# BBallboard.net
KiCad netlist of a schematic drawn in EAGLE
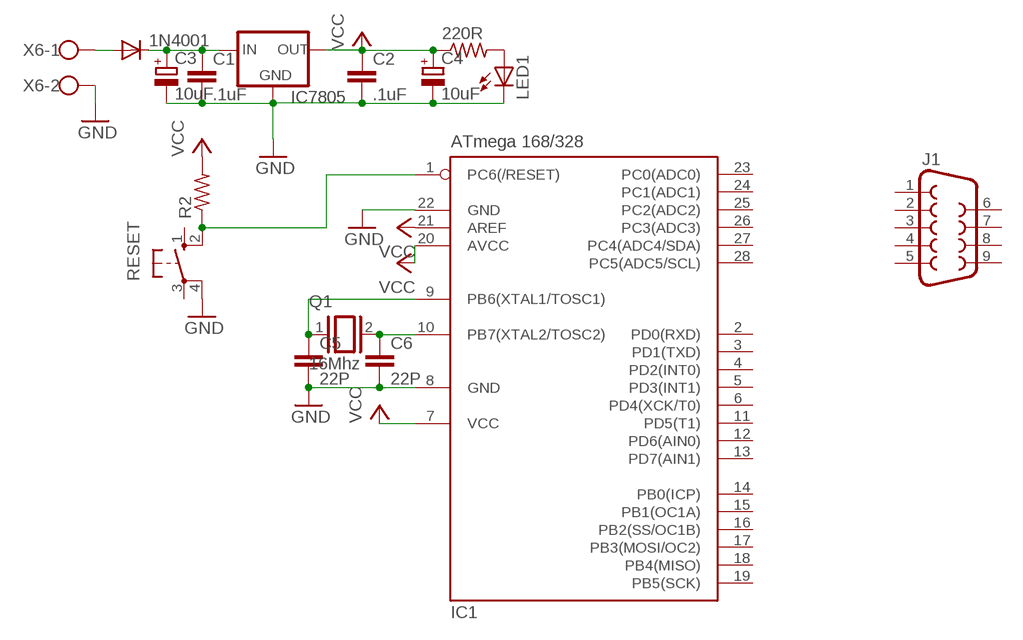
[diagram p0: schematic, sheet 1]

(export (version "E")
  (design (tool "Eeschema 10.0.6"))
  (components
    (comp (ref "1N4001")
      (value "BYT85")
      (footprint "eagle-import:DO220S")
      (libsource (lib "eagle-import") (part "BYT85"))
    )
    (comp (ref "220R")
      (value "R-US_0204/7")
      (footprint "eagle-import:0204_7")
      (libsource (lib "eagle-import") (part "R-US_0204/7"))
    )
    (comp (ref "C1")
      (value ".1uF")
      (footprint "eagle-import:C025-024X044")
      (libsource (lib "eagle-import") (part "C-EU025-024X044"))
    )
    (comp (ref "C2")
      (value ".1uF")
      (footprint "eagle-import:C025-024X044")
      (libsource (lib "eagle-import") (part "C-EU025-024X044"))
    )
    (comp (ref "C3")
      (value "10uF")
      (footprint "eagle-import:E1,8-4")
      (libsource (lib "eagle-import") (part "CPOL-EUE1.8-4"))
    )
    (comp (ref "C4")
      (value "10uF")
      (footprint "eagle-import:E1,8-4")
      (libsource (lib "eagle-import") (part "CPOL-EUE1.8-4"))
    )
    (comp (ref "C5")
      (value "22P")
      (footprint "eagle-import:C025-024X044")
      (libsource (lib "eagle-import") (part "C-EU025-024X044"))
    )
    (comp (ref "C6")
      (value "22P")
      (footprint "eagle-import:C025-024X044")
      (libsource (lib "eagle-import") (part "C-EU025-024X044"))
    )
    (comp (ref "IC1")
      (value "ATmega 168/328")
      (footprint "eagle-import:DIL28-3")
      (libsource (lib "eagle-import") (part "MEGA8-P"))
    )
    (comp (ref "IC7805")
      (value "78XXS")
      (footprint "eagle-import:78XXS")
      (libsource (lib "eagle-import") (part "78XXS"))
    )
    (comp (ref "J1")
      (value "DB9FEMALE")
      (footprint "eagle-import:DB9")
      (libsource (lib "eagle-import") (part "DB9FEMALE"))
    )
    (comp (ref "LED1")
      (value "LED3MM")
      (footprint "eagle-import:LED3MM")
      (libsource (lib "eagle-import") (part "LED3MM"))
    )
    (comp (ref "Q1")
      (value "16Mhz")
      (footprint "eagle-import:QS")
      (libsource (lib "eagle-import") (part "XTAL/S"))
    )
    (comp (ref "R2")
      (value "R-US_0204/7")
      (footprint "eagle-import:0204_7")
      (libsource (lib "eagle-import") (part "R-US_0204/7"))
    )
    (comp (ref "RESET")
      (value "10-XX")
      (footprint "eagle-import:B3F-10XX")
      (libsource (lib "eagle-import") (part "10-XX"))
    )
    (comp (ref "X6")
      (value "W237-102")
      (footprint "eagle-import:W237-102")
      (libsource (lib "eagle-import") (part "W237-102"))
    )
  )
  (nets
    (net (code "1") (name "GND") (class "Default")
      (node (ref "C1") (pin "2") (pinfunction "2_2") (pintype "passive"))
      (node (ref "C2") (pin "2") (pinfunction "2_2") (pintype "passive"))
      (node (ref "C3") (pin "-") (pinfunction "-_-") (pintype "passive"))
      (node (ref "C4") (pin "-") (pinfunction "-_-") (pintype "passive"))
      (node (ref "C5") (pin "2") (pinfunction "2_2") (pintype "passive"))
      (node (ref "C6") (pin "2") (pinfunction "2_2") (pintype "passive"))
      (node (ref "IC1") (pin "22") (pinfunction "GND_22") (pintype "power_in"))
      (node (ref "IC1") (pin "8") (pinfunction "GND_8") (pintype "power_in"))
      (node (ref "IC7805") (pin "GND") (pinfunction "GND_GND") (pintype "input"))
      (node (ref "LED1") (pin "K") (pinfunction "C_K") (pintype "passive"))
      (node (ref "RESET") (pin "4") (pinfunction "P1_4") (pintype "passive"))
      (node (ref "X6") (pin "2") (pinfunction "KL_2") (pintype "passive"))
    )
    (net (code "2") (name "Net-(1N4001-PadC)") (class "Default")
      (node (ref "1N4001") (pin "C") (pinfunction "C_C") (pintype "passive"))
      (node (ref "C1") (pin "1") (pinfunction "1_1") (pintype "passive"))
      (node (ref "C3") (pin "+") (pinfunction "+_+") (pintype "passive"))
      (node (ref "IC7805") (pin "IN") (pinfunction "IN_IN") (pintype "input"))
    )
    (net (code "3") (name "Net-(220R-Pad2)") (class "Default")
      (node (ref "220R") (pin "2") (pinfunction "2_2") (pintype "passive"))
      (node (ref "LED1") (pin "A") (pinfunction "A_A") (pintype "passive"))
    )
    (net (code "4") (name "Net-(IC1-PB6(XTAL1{slash}TOSC1))") (class "Default")
      (node (ref "C5") (pin "1") (pinfunction "1_1") (pintype "passive"))
      (node (ref "IC1") (pin "9") (pinfunction "PB6(XTAL1/TOSC1)_9") (pintype "bidirectional"))
      (node (ref "Q1") (pin "1") (pinfunction "1_1") (pintype "passive"))
    )
    (net (code "5") (name "Net-(IC1-PB7(XTAL2{slash}TOSC2))") (class "Default")
      (node (ref "C6") (pin "1") (pinfunction "1_1") (pintype "passive"))
      (node (ref "IC1") (pin "10") (pinfunction "PB7(XTAL2/TOSC2)_10") (pintype "bidirectional"))
      (node (ref "Q1") (pin "2") (pinfunction "2_2") (pintype "passive"))
    )
    (net (code "6") (name "Net-(IC1-PC6({slash}RESET))") (class "Default")
      (node (ref "IC1") (pin "1") (pinfunction "PC6(/RESET)_1") (pintype "bidirectional"))
      (node (ref "R2") (pin "1") (pinfunction "1_1") (pintype "passive"))
      (node (ref "RESET") (pin "2") (pinfunction "S1_2") (pintype "passive"))
    )
    (net (code "7") (name "Net-(X6A-KL)") (class "Default")
      (node (ref "1N4001") (pin "A") (pinfunction "A_A") (pintype "passive"))
      (node (ref "X6") (pin "1") (pinfunction "KL_1") (pintype "passive"))
    )
    (net (code "8") (name "VCC") (class "Default")
      (node (ref "220R") (pin "1") (pinfunction "1_1") (pintype "passive"))
      (node (ref "C2") (pin "1") (pinfunction "1_1") (pintype "passive"))
      (node (ref "C4") (pin "+") (pinfunction "+_+") (pintype "passive"))
      (node (ref "IC1") (pin "20") (pinfunction "AVCC_20") (pintype "power_in"))
      (node (ref "IC1") (pin "21") (pinfunction "AREF_21") (pintype "passive"))
      (node (ref "IC1") (pin "7") (pinfunction "VCC_7") (pintype "power_in"))
      (node (ref "IC7805") (pin "OUT") (pinfunction "OUT_OUT") (pintype "passive"))
      (node (ref "R2") (pin "2") (pinfunction "2_2") (pintype "passive"))
    )
    (net (code "9") (name "unconnected-(IC1-PB0(ICP)-Pad14)") (class "Default")
      (node (ref "IC1") (pin "14") (pinfunction "PB0(ICP)_14") (pintype "bidirectional"))
    )
    (net (code "10") (name "unconnected-(IC1-PB1(OC1A)-Pad15)") (class "Default")
      (node (ref "IC1") (pin "15") (pinfunction "PB1(OC1A)_15") (pintype "bidirectional"))
    )
    (net (code "11") (name "unconnected-(IC1-PB2(SS{slash}OC1B)-Pad16)") (class "Default")
      (node (ref "IC1") (pin "16") (pinfunction "PB2(SS/OC1B)_16") (pintype "bidirectional"))
    )
    (net (code "12") (name "unconnected-(IC1-PB3(MOSI{slash}OC2)-Pad17)") (class "Default")
      (node (ref "IC1") (pin "17") (pinfunction "PB3(MOSI/OC2)_17") (pintype "bidirectional"))
    )
    (net (code "13") (name "unconnected-(IC1-PB4(MISO)-Pad18)") (class "Default")
      (node (ref "IC1") (pin "18") (pinfunction "PB4(MISO)_18") (pintype "bidirectional"))
    )
    (net (code "14") (name "unconnected-(IC1-PB5(SCK)-Pad19)") (class "Default")
      (node (ref "IC1") (pin "19") (pinfunction "PB5(SCK)_19") (pintype "bidirectional"))
    )
    (net (code "15") (name "unconnected-(IC1-PC0(ADC0)-Pad23)") (class "Default")
      (node (ref "IC1") (pin "23") (pinfunction "PC0(ADC0)_23") (pintype "bidirectional"))
    )
    (net (code "16") (name "unconnected-(IC1-PC1(ADC1)-Pad24)") (class "Default")
      (node (ref "IC1") (pin "24") (pinfunction "PC1(ADC1)_24") (pintype "bidirectional"))
    )
    (net (code "17") (name "unconnected-(IC1-PC2(ADC2)-Pad25)") (class "Default")
      (node (ref "IC1") (pin "25") (pinfunction "PC2(ADC2)_25") (pintype "bidirectional"))
    )
    (net (code "18") (name "unconnected-(IC1-PC3(ADC3)-Pad26)") (class "Default")
      (node (ref "IC1") (pin "26") (pinfunction "PC3(ADC3)_26") (pintype "bidirectional"))
    )
    (net (code "19") (name "unconnected-(IC1-PC4(ADC4{slash}SDA)-Pad27)") (class "Default")
      (node (ref "IC1") (pin "27") (pinfunction "PC4(ADC4/SDA)_27") (pintype "bidirectional"))
    )
    (net (code "20") (name "unconnected-(IC1-PC5(ADC5{slash}SCL)-Pad28)") (class "Default")
      (node (ref "IC1") (pin "28") (pinfunction "PC5(ADC5/SCL)_28") (pintype "bidirectional"))
    )
    (net (code "21") (name "unconnected-(IC1-PD0(RXD)-Pad2)") (class "Default")
      (node (ref "IC1") (pin "2") (pinfunction "PD0(RXD)_2") (pintype "bidirectional"))
    )
    (net (code "22") (name "unconnected-(IC1-PD1(TXD)-Pad3)") (class "Default")
      (node (ref "IC1") (pin "3") (pinfunction "PD1(TXD)_3") (pintype "bidirectional"))
    )
    (net (code "23") (name "unconnected-(IC1-PD2(INT0)-Pad4)") (class "Default")
      (node (ref "IC1") (pin "4") (pinfunction "PD2(INT0)_4") (pintype "bidirectional"))
    )
    (net (code "24") (name "unconnected-(IC1-PD3(INT1)-Pad5)") (class "Default")
      (node (ref "IC1") (pin "5") (pinfunction "PD3(INT1)_5") (pintype "bidirectional"))
    )
    (net (code "25") (name "unconnected-(IC1-PD4(XCK{slash}T0)-Pad6)") (class "Default")
      (node (ref "IC1") (pin "6") (pinfunction "PD4(XCK/T0)_6") (pintype "bidirectional"))
    )
    (net (code "26") (name "unconnected-(IC1-PD5(T1)-Pad11)") (class "Default")
      (node (ref "IC1") (pin "11") (pinfunction "PD5(T1)_11") (pintype "bidirectional"))
    )
    (net (code "27") (name "unconnected-(IC1-PD6(AIN0)-Pad12)") (class "Default")
      (node (ref "IC1") (pin "12") (pinfunction "PD6(AIN0)_12") (pintype "bidirectional"))
    )
    (net (code "28") (name "unconnected-(IC1-PD7(AIN1)-Pad13)") (class "Default")
      (node (ref "IC1") (pin "13") (pinfunction "PD7(AIN1)_13") (pintype "bidirectional"))
    )
    (net (code "29") (name "unconnected-(J1-Pad1)") (class "Default")
      (node (ref "J1") (pin "1") (pinfunction "1_1") (pintype "passive"))
    )
    (net (code "30") (name "unconnected-(J1-Pad2)") (class "Default")
      (node (ref "J1") (pin "2") (pinfunction "2_2") (pintype "passive"))
    )
    (net (code "31") (name "unconnected-(J1-Pad3)") (class "Default")
      (node (ref "J1") (pin "3") (pinfunction "3_3") (pintype "passive"))
    )
    (net (code "32") (name "unconnected-(J1-Pad4)") (class "Default")
      (node (ref "J1") (pin "4") (pinfunction "4_4") (pintype "passive"))
    )
    (net (code "33") (name "unconnected-(J1-Pad5)") (class "Default")
      (node (ref "J1") (pin "5") (pinfunction "5_5") (pintype "passive"))
    )
    (net (code "34") (name "unconnected-(J1-Pad6)") (class "Default")
      (node (ref "J1") (pin "6") (pinfunction "6_6") (pintype "passive"))
    )
    (net (code "35") (name "unconnected-(J1-Pad7)") (class "Default")
      (node (ref "J1") (pin "7") (pinfunction "7_7") (pintype "passive"))
    )
    (net (code "36") (name "unconnected-(J1-Pad8)") (class "Default")
      (node (ref "J1") (pin "8") (pinfunction "8_8") (pintype "passive"))
    )
    (net (code "37") (name "unconnected-(J1-Pad9)") (class "Default")
      (node (ref "J1") (pin "9") (pinfunction "9_9") (pintype "passive"))
    )
    (net (code "38") (name "unconnected-(RESET-P-Pad3)") (class "Default")
      (node (ref "RESET") (pin "3") (pinfunction "P_3") (pintype "passive"))
    )
    (net (code "39") (name "unconnected-(RESET-S-Pad1)") (class "Default")
      (node (ref "RESET") (pin "1") (pinfunction "S_1") (pintype "passive"))
    )
  )
)
